# QCopterNano_Sch.net
KiCad netlist of a schematic drawn in Altium Designer
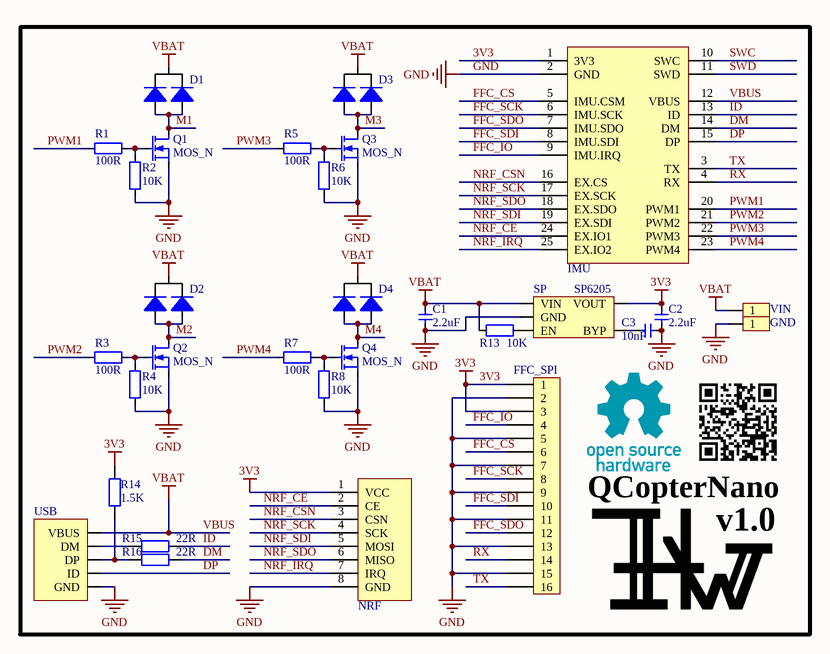
[diagram p0: QCopterNano_Sch.SchDoc]

(export (version "E")
  (design (tool "Eeschema 10.0.6"))
  (components
    (comp (ref "C1")
      (value "2.2uF")
      (footprint "PCB_Passive:CAP_0603")
      (description "Capacitor")
      (fields (field (name "Comment") "Cap_0603"))
      (libsource (lib "SCH_Passive") (part "Cap_0603"))
    )
    (comp (ref "C2")
      (value "2.2uF")
      (footprint "PCB_Passive:CAP_0603")
      (description "Capacitor")
      (fields (field (name "Comment") "Cap_0603"))
      (libsource (lib "SCH_Passive") (part "Cap_0603"))
    )
    (comp (ref "C3")
      (value "10nF")
      (footprint "PCB_Passive:CAP_0603")
      (description "Capacitor")
      (fields (field (name "Comment") "Cap_0603"))
      (libsource (lib "SCH_Passive") (part "Cap_0603"))
    )
    (comp (ref "D1")
      (value "Diode_Schottky2")
      (footprint "PCB_Active:SOT23-3")
      (description "Diode")
      (libsource (lib "SCH_Active") (part "Diode_Schottky2"))
    )
    (comp (ref "D2")
      (value "Diode_Schottky2")
      (footprint "PCB_Active:SOT23-3")
      (description "Diode")
      (libsource (lib "SCH_Active") (part "Diode_Schottky2"))
    )
    (comp (ref "D3")
      (value "Diode_Schottky2")
      (footprint "PCB_Active:SOT23-3")
      (description "Diode")
      (libsource (lib "SCH_Active") (part "Diode_Schottky2"))
    )
    (comp (ref "D4")
      (value "Diode_Schottky2")
      (footprint "PCB_Active:SOT23-3")
      (description "Diode")
      (libsource (lib "SCH_Active") (part "Diode_Schottky2"))
    )
    (comp (ref "FFC_SPI")
      (value "FFC_0.5_16")
      (footprint "PCB_Connector:FFC_0.5_16")
      (description "FFC")
      (libsource (lib "SCH_Connector") (part "FFC_0.5_16"))
    )
    (comp (ref "GND")
      (value "HDR1X1_180_2.54")
      (footprint "PCB_Connector:HDR1X1_180_2.54")
      (description "Header")
      (libsource (lib "SCH_Connector") (part "HDR1X1_180_2.54"))
    )
    (comp (ref "HW")
      (value "HW")
      (footprint "PCB_Logo:Logo_HW_v2.0")
      (description "Logo")
      (libsource (lib "SCH_Logo") (part "HW"))
    )
    (comp (ref "IMU")
      (value "SmartIMU_Full")
      (footprint "PCB_Module:SMART_IMU_FULL")
      (description "Module")
      (libsource (lib "SCH_Module") (part "SmartIMU_Full"))
    )
    (comp (ref "NRF")
      (value "nRF24L01P_PA_LNA")
      (footprint "PCB_Module:NRF24L01P_PA_LNA")
      (description "Module")
      (libsource (lib "SCH_Module") (part "nRF24L01P_PA_LNA"))
    )
    (comp (ref "ORCODE")
      (value "QCopterNano_ORCODE")
      (description "Logo")
      (libsource (lib "SCH_Logo") (part "QCopterNano_ORCODE"))
    )
    (comp (ref "OSHW") (value "OSHW") (description "Logo") (libsource (lib "SCH_Logo") (part "OSHW")))
    (comp (ref "Q1")
      (value "MOS_N")
      (footprint "PCB_Active:SOT23-3")
      (description "MOSFET")
      (fields (field (name "PUBLISHER") "Altium Limited"))
      (libsource (lib "SCH_Active") (part "MOSFET_N"))
    )
    (comp (ref "Q2")
      (value "MOS_N")
      (footprint "PCB_Active:SOT23-3")
      (description "MOSFET")
      (fields (field (name "PUBLISHER") "Altium Limited"))
      (libsource (lib "SCH_Active") (part "MOSFET_N"))
    )
    (comp (ref "Q3")
      (value "MOS_N")
      (footprint "PCB_Active:SOT23-3")
      (description "MOSFET")
      (fields (field (name "PUBLISHER") "Altium Limited"))
      (libsource (lib "SCH_Active") (part "MOSFET_N"))
    )
    (comp (ref "Q4")
      (value "MOS_N")
      (footprint "PCB_Active:SOT23-3")
      (description "MOSFET")
      (fields (field (name "PUBLISHER") "Altium Limited"))
      (libsource (lib "SCH_Active") (part "MOSFET_N"))
    )
    (comp (ref "R1")
      (value "100R")
      (footprint "PCB_Passive:RES_0603")
      (description "Resistor")
      (fields (field (name "Comment") "Res_0603"))
      (libsource (lib "") (part "Res_0603_1"))
    )
    (comp (ref "R2")
      (value "10K")
      (footprint "PCB_Passive:RES_0603")
      (description "Resistor")
      (fields (field (name "Comment") "Res_0603"))
      (libsource (lib "SCH_Passive") (part "Res_0603"))
    )
    (comp (ref "R3")
      (value "100R")
      (footprint "PCB_Passive:RES_0603")
      (description "Resistor")
      (fields (field (name "Comment") "Res_0603"))
      (libsource (lib "") (part "Res_0603_1"))
    )
    (comp (ref "R4")
      (value "10K")
      (footprint "PCB_Passive:RES_0603")
      (description "Resistor")
      (fields (field (name "Comment") "Res_0603"))
      (libsource (lib "SCH_Passive") (part "Res_0603"))
    )
    (comp (ref "R5")
      (value "100R")
      (footprint "PCB_Passive:RES_0603")
      (description "Resistor")
      (fields (field (name "Comment") "Res_0603"))
      (libsource (lib "") (part "Res_0603_1"))
    )
    (comp (ref "R6")
      (value "10K")
      (footprint "PCB_Passive:RES_0603")
      (description "Resistor")
      (fields (field (name "Comment") "Res_0603"))
      (libsource (lib "SCH_Passive") (part "Res_0603"))
    )
    (comp (ref "R7")
      (value "100R")
      (footprint "PCB_Passive:RES_0603")
      (description "Resistor")
      (fields (field (name "Comment") "Res_0603"))
      (libsource (lib "") (part "Res_0603_1"))
    )
    (comp (ref "R8")
      (value "10K")
      (footprint "PCB_Passive:RES_0603")
      (description "Resistor")
      (fields (field (name "Comment") "Res_0603"))
      (libsource (lib "SCH_Passive") (part "Res_0603"))
    )
    (comp (ref "R13")
      (value "10K")
      (footprint "PCB_Passive:RES_0603")
      (description "Resistor")
      (fields (field (name "Comment") "Res_0603"))
      (libsource (lib "") (part "Res_0603_1"))
    )
    (comp (ref "R14")
      (value "1.5K")
      (footprint "PCB_Passive:RES_0603")
      (description "Resistor")
      (fields (field (name "Comment") "Res_0603"))
      (libsource (lib "") (part "Res_0603_2"))
    )
    (comp (ref "R15")
      (value "22R")
      (footprint "PCB_Passive:RES_0603")
      (description "Resistor")
      (fields (field (name "Comment") "Res_0603"))
      (libsource (lib "") (part "Res_0603_3"))
    )
    (comp (ref "R16")
      (value "22R")
      (footprint "PCB_Passive:RES_0603")
      (description "Resistor")
      (fields (field (name "Comment") "Res_0603"))
      (libsource (lib "") (part "Res_0603_3"))
    )
    (comp (ref "SP")
      (value "SP6205")
      (footprint "PCB_IC:SOT23-5")
      (description "Power")
      (libsource (lib "SCH_IC") (part "SP6205"))
    )
    (comp (ref "USB")
      (value "USB_Micro")
      (footprint "PCB_USB:USB_Micro-AB")
      (description "USB")
      (libsource (lib "SCH_USB") (part "USB_Micro"))
    )
    (comp (ref "VIN")
      (value "HDR1X1_180_2.54")
      (footprint "PCB_Connector:HDR1X1_180_2.54")
      (description "Header")
      (libsource (lib "SCH_Connector") (part "HDR1X1_180_2.54"))
    )
  )
  (nets
    (net (code "1") (name "/DM") (class "Default")
      (node (ref "IMU") (pin "14") (pinfunction "DM_14") (pintype "passive"))
      (node (ref "R16") (pin "2") (pinfunction "2_2") (pintype "passive"))
    )
    (net (code "2") (name "/DP") (class "Default")
      (node (ref "IMU") (pin "15") (pinfunction "DP_15") (pintype "passive"))
      (node (ref "USB") (pin "4") (pinfunction "ID_4") (pintype "passive"))
    )
    (net (code "3") (name "/FFC_CS") (class "Default")
      (node (ref "FFC_SPI") (pin "6") (pinfunction "6_6") (pintype "passive"))
      (node (ref "IMU") (pin "5") (pinfunction "IMU.CSM_5") (pintype "passive"))
    )
    (net (code "4") (name "/FFC_IO") (class "Default")
      (node (ref "FFC_SPI") (pin "4") (pinfunction "4_4") (pintype "passive"))
      (node (ref "IMU") (pin "9") (pinfunction "IMU.IRQ_9") (pintype "passive"))
    )
    (net (code "5") (name "/FFC_SCK") (class "Default")
      (node (ref "FFC_SPI") (pin "8") (pinfunction "8_8") (pintype "passive"))
      (node (ref "IMU") (pin "6") (pinfunction "IMU.SCK_6") (pintype "passive"))
    )
    (net (code "6") (name "/FFC_SDI") (class "Default")
      (node (ref "FFC_SPI") (pin "10") (pinfunction "10_10") (pintype "passive"))
      (node (ref "IMU") (pin "8") (pinfunction "IMU.SDI_8") (pintype "passive"))
    )
    (net (code "7") (name "/FFC_SDO") (class "Default")
      (node (ref "FFC_SPI") (pin "12") (pinfunction "12_12") (pintype "passive"))
      (node (ref "IMU") (pin "7") (pinfunction "IMU.SDO_7") (pintype "passive"))
    )
    (net (code "8") (name "/ID") (class "Default")
      (node (ref "IMU") (pin "13") (pinfunction "ID_13") (pintype "passive"))
      (node (ref "R15") (pin "2") (pinfunction "2_2") (pintype "passive"))
    )
    (net (code "9") (name "/M1") (class "Default")
      (node (ref "D1") (pin "1") (pinfunction "A_1") (pintype "passive"))
      (node (ref "D1") (pin "2") (pinfunction "A_2") (pintype "passive"))
      (node (ref "Q1") (pin "3") (pinfunction "D_3") (pintype "passive"))
    )
    (net (code "10") (name "/M2") (class "Default")
      (node (ref "D2") (pin "1") (pinfunction "A_1") (pintype "passive"))
      (node (ref "D2") (pin "2") (pinfunction "A_2") (pintype "passive"))
      (node (ref "Q2") (pin "3") (pinfunction "D_3") (pintype "passive"))
    )
    (net (code "11") (name "/M3") (class "Default")
      (node (ref "D3") (pin "1") (pinfunction "A_1") (pintype "passive"))
      (node (ref "D3") (pin "2") (pinfunction "A_2") (pintype "passive"))
      (node (ref "Q3") (pin "3") (pinfunction "D_3") (pintype "passive"))
    )
    (net (code "12") (name "/M4") (class "Default")
      (node (ref "D4") (pin "1") (pinfunction "A_1") (pintype "passive"))
      (node (ref "D4") (pin "2") (pinfunction "A_2") (pintype "passive"))
      (node (ref "Q4") (pin "3") (pinfunction "D_3") (pintype "passive"))
    )
    (net (code "13") (name "/NRF_CE") (class "Default")
      (node (ref "IMU") (pin "24") (pinfunction "EX.IO1_24") (pintype "passive"))
      (node (ref "NRF") (pin "2") (pinfunction "CE_2") (pintype "passive"))
    )
    (net (code "14") (name "/NRF_CSN") (class "Default")
      (node (ref "IMU") (pin "16") (pinfunction "EX.CS_16") (pintype "passive"))
      (node (ref "NRF") (pin "3") (pinfunction "CSN_3") (pintype "passive"))
    )
    (net (code "15") (name "/NRF_IRQ") (class "Default")
      (node (ref "IMU") (pin "25") (pinfunction "EX.IO2_25") (pintype "passive"))
      (node (ref "NRF") (pin "7") (pinfunction "IRQ_7") (pintype "passive"))
    )
    (net (code "16") (name "/NRF_SCK") (class "Default")
      (node (ref "IMU") (pin "17") (pinfunction "EX.SCK_17") (pintype "passive"))
      (node (ref "NRF") (pin "4") (pinfunction "SCK_4") (pintype "passive"))
    )
    (net (code "17") (name "/NRF_SDI") (class "Default")
      (node (ref "IMU") (pin "19") (pinfunction "EX.SDI_19") (pintype "passive"))
      (node (ref "NRF") (pin "5") (pinfunction "MOSI_5") (pintype "passive"))
    )
    (net (code "18") (name "/NRF_SDO") (class "Default")
      (node (ref "IMU") (pin "18") (pinfunction "EX.SDO_18") (pintype "passive"))
      (node (ref "NRF") (pin "6") (pinfunction "MISO_6") (pintype "passive"))
    )
    (net (code "19") (name "/PWM1") (class "Default")
      (node (ref "IMU") (pin "20") (pinfunction "PWM1_20") (pintype "passive"))
      (node (ref "R1") (pin "1") (pinfunction "1_1") (pintype "passive"))
    )
    (net (code "20") (name "/PWM2") (class "Default")
      (node (ref "IMU") (pin "21") (pinfunction "PWM2_21") (pintype "passive"))
      (node (ref "R3") (pin "1") (pinfunction "1_1") (pintype "passive"))
    )
    (net (code "21") (name "/PWM3") (class "Default")
      (node (ref "IMU") (pin "22") (pinfunction "PWM3_22") (pintype "passive"))
      (node (ref "R5") (pin "1") (pinfunction "1_1") (pintype "passive"))
    )
    (net (code "22") (name "/PWM4") (class "Default")
      (node (ref "IMU") (pin "23") (pinfunction "PWM4_23") (pintype "passive"))
      (node (ref "R7") (pin "1") (pinfunction "1_1") (pintype "passive"))
    )
    (net (code "23") (name "/RX") (class "Default")
      (node (ref "FFC_SPI") (pin "14") (pinfunction "14_14") (pintype "passive"))
      (node (ref "IMU") (pin "4") (pinfunction "RX_4") (pintype "passive"))
    )
    (net (code "24") (name "/SWC") (class "Default")
      (node (ref "IMU") (pin "10") (pinfunction "SWC_10") (pintype "passive"))
    )
    (net (code "25") (name "/SWD") (class "Default")
      (node (ref "IMU") (pin "11") (pinfunction "SWD_11") (pintype "passive"))
    )
    (net (code "26") (name "/TX") (class "Default")
      (node (ref "FFC_SPI") (pin "16") (pinfunction "16_16") (pintype "passive"))
      (node (ref "IMU") (pin "3") (pinfunction "TX_3") (pintype "passive"))
    )
    (net (code "27") (name "3V3") (class "Default")
      (node (ref "C2") (pin "2") (pinfunction "2_2") (pintype "passive"))
      (node (ref "FFC_SPI") (pin "1") (pinfunction "1_1") (pintype "passive"))
      (node (ref "FFC_SPI") (pin "3") (pinfunction "3_3") (pintype "passive"))
      (node (ref "IMU") (pin "1") (pinfunction "3V3_1") (pintype "passive"))
      (node (ref "NRF") (pin "1") (pinfunction "VCC_1") (pintype "passive"))
      (node (ref "R14") (pin "2") (pinfunction "2_2") (pintype "passive"))
      (node (ref "SP") (pin "5") (pinfunction "VOUT_5") (pintype "power_in"))
    )
    (net (code "28") (name "GND") (class "Default")
      (node (ref "C1") (pin "1") (pinfunction "1_1") (pintype "passive"))
      (node (ref "C2") (pin "1") (pinfunction "1_1") (pintype "passive"))
      (node (ref "C3") (pin "1") (pinfunction "1_1") (pintype "passive"))
      (node (ref "FFC_SPI") (pin "11") (pinfunction "11_11") (pintype "passive"))
      (node (ref "FFC_SPI") (pin "13") (pinfunction "13_13") (pintype "passive"))
      (node (ref "FFC_SPI") (pin "15") (pinfunction "15_15") (pintype "passive"))
      (node (ref "FFC_SPI") (pin "2") (pinfunction "2_2") (pintype "passive"))
      (node (ref "FFC_SPI") (pin "5") (pinfunction "5_5") (pintype "passive"))
      (node (ref "FFC_SPI") (pin "7") (pinfunction "7_7") (pintype "passive"))
      (node (ref "FFC_SPI") (pin "9") (pinfunction "9_9") (pintype "passive"))
      (node (ref "GND") (pin "1") (pinfunction "1_1") (pintype "passive"))
      (node (ref "IMU") (pin "2") (pinfunction "GND_2") (pintype "passive"))
      (node (ref "NRF") (pin "8") (pinfunction "GND_8") (pintype "passive"))
      (node (ref "Q1") (pin "2") (pinfunction "S_2") (pintype "passive"))
      (node (ref "Q2") (pin "2") (pinfunction "S_2") (pintype "passive"))
      (node (ref "Q3") (pin "2") (pinfunction "S_2") (pintype "passive"))
      (node (ref "Q4") (pin "2") (pinfunction "S_2") (pintype "passive"))
      (node (ref "R2") (pin "1") (pinfunction "1_1") (pintype "passive"))
      (node (ref "R4") (pin "1") (pinfunction "1_1") (pintype "passive"))
      (node (ref "R6") (pin "1") (pinfunction "1_1") (pintype "passive"))
      (node (ref "R8") (pin "1") (pinfunction "1_1") (pintype "passive"))
      (node (ref "SP") (pin "2") (pinfunction "GND_2") (pintype "power_in"))
      (node (ref "USB") (pin "5") (pinfunction "GND_5") (pintype "passive"))
    )
    (net (code "29") (name "Net-(Q1-G)") (class "Default")
      (node (ref "Q1") (pin "1") (pinfunction "G_1") (pintype "passive"))
      (node (ref "R1") (pin "2") (pinfunction "2_2") (pintype "passive"))
      (node (ref "R2") (pin "2") (pinfunction "2_2") (pintype "passive"))
    )
    (net (code "30") (name "Net-(Q2-G)") (class "Default")
      (node (ref "Q2") (pin "1") (pinfunction "G_1") (pintype "passive"))
      (node (ref "R3") (pin "2") (pinfunction "2_2") (pintype "passive"))
      (node (ref "R4") (pin "2") (pinfunction "2_2") (pintype "passive"))
    )
    (net (code "31") (name "Net-(Q3-G)") (class "Default")
      (node (ref "Q3") (pin "1") (pinfunction "G_1") (pintype "passive"))
      (node (ref "R5") (pin "2") (pinfunction "2_2") (pintype "passive"))
      (node (ref "R6") (pin "2") (pinfunction "2_2") (pintype "passive"))
    )
    (net (code "32") (name "Net-(Q4-G)") (class "Default")
      (node (ref "Q4") (pin "1") (pinfunction "G_1") (pintype "passive"))
      (node (ref "R7") (pin "2") (pinfunction "2_2") (pintype "passive"))
      (node (ref "R8") (pin "2") (pinfunction "2_2") (pintype "passive"))
    )
    (net (code "33") (name "Net-(SP-BYP)") (class "Default")
      (node (ref "C3") (pin "2") (pinfunction "2_2") (pintype "passive"))
      (node (ref "SP") (pin "4") (pinfunction "BYP_4") (pintype "power_in"))
    )
    (net (code "34") (name "Net-(SP-EN)") (class "Default")
      (node (ref "R13") (pin "2") (pinfunction "2_2") (pintype "passive"))
      (node (ref "SP") (pin "3") (pinfunction "EN_3") (pintype "power_in"))
    )
    (net (code "35") (name "Net-(USB-DM)") (class "Default")
      (node (ref "R15") (pin "1") (pinfunction "1_1") (pintype "passive"))
      (node (ref "USB") (pin "2") (pinfunction "DM_2") (pintype "passive"))
    )
    (net (code "36") (name "Net-(USB-DP)") (class "Default")
      (node (ref "R14") (pin "1") (pinfunction "1_1") (pintype "passive"))
      (node (ref "R16") (pin "1") (pinfunction "1_1") (pintype "passive"))
      (node (ref "USB") (pin "3") (pinfunction "DP_3") (pintype "passive"))
    )
    (net (code "37") (name "VBAT") (class "Default")
      (node (ref "C1") (pin "2") (pinfunction "2_2") (pintype "passive"))
      (node (ref "D1") (pin "3") (pinfunction "K_3") (pintype "passive"))
      (node (ref "D2") (pin "3") (pinfunction "K_3") (pintype "passive"))
      (node (ref "D3") (pin "3") (pinfunction "K_3") (pintype "passive"))
      (node (ref "D4") (pin "3") (pinfunction "K_3") (pintype "passive"))
      (node (ref "IMU") (pin "12") (pinfunction "VBUS_12") (pintype "passive"))
      (node (ref "R13") (pin "1") (pinfunction "1_1") (pintype "passive"))
      (node (ref "SP") (pin "1") (pinfunction "VIN_1") (pintype "power_in"))
      (node (ref "USB") (pin "1") (pinfunction "VBUS_1") (pintype "passive"))
      (node (ref "VIN") (pin "1") (pinfunction "1_1") (pintype "passive"))
    )
  )
)
